# A4_INSAGE_01.net
KiCad netlist of a schematic drawn in Altium Designer
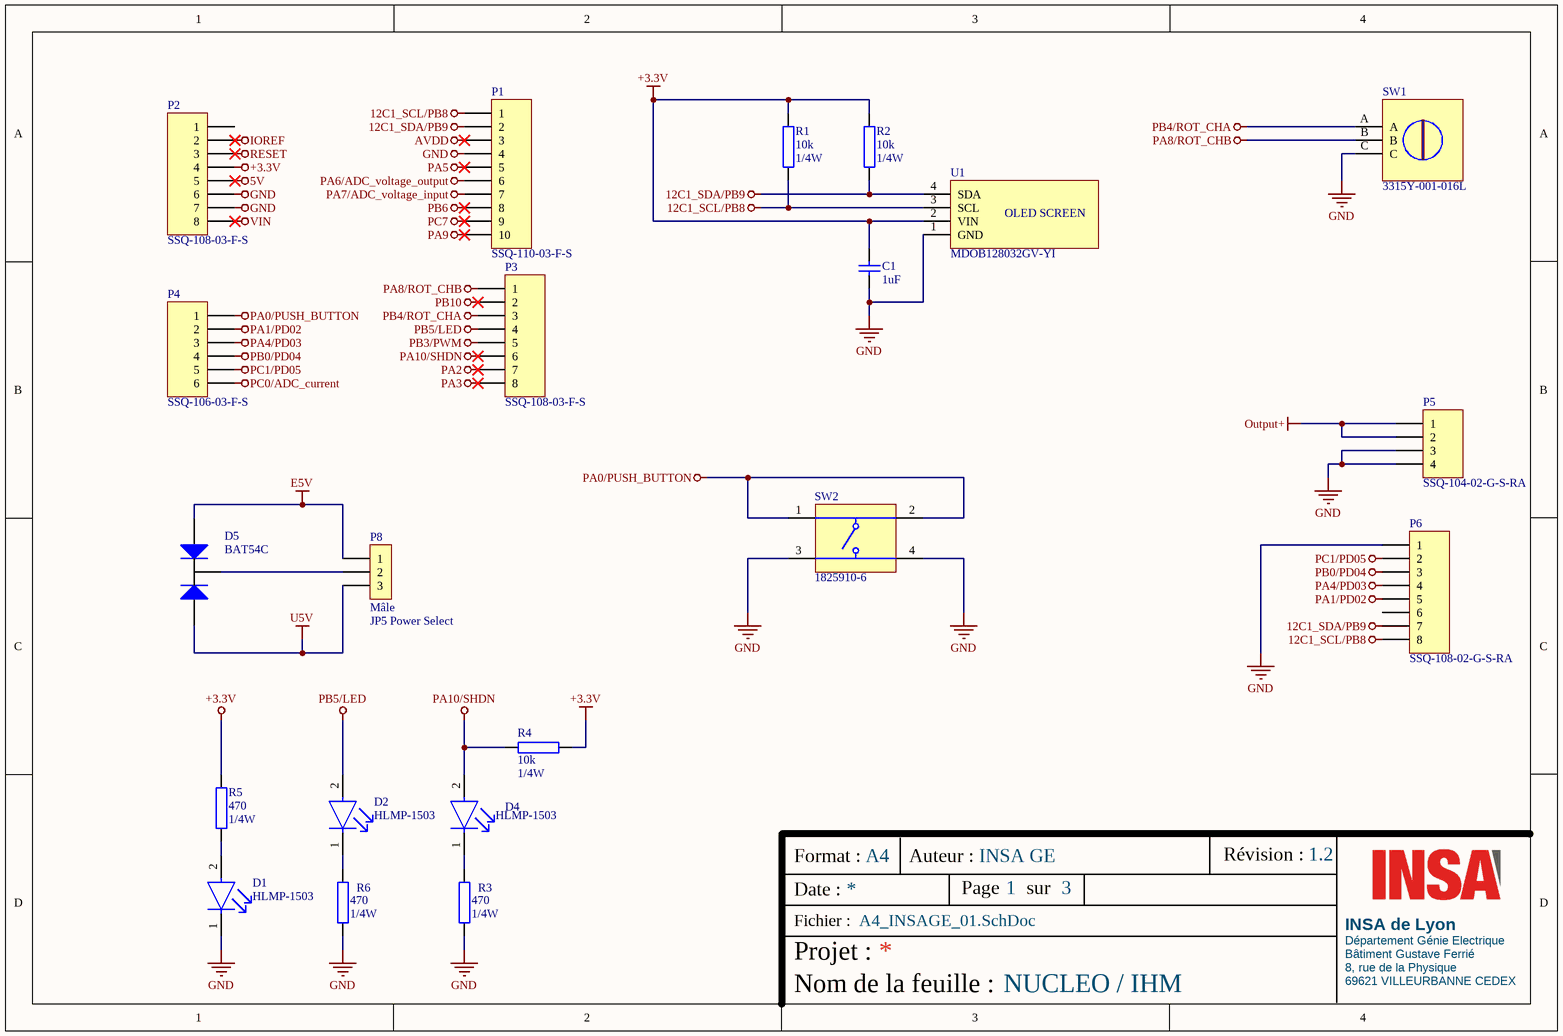
[diagram p0: A4_INSAGE_01.SchDoc]

(export (version "E")
  (design (tool "Eeschema 10.0.6"))
  (components
    (comp (ref "C1")
      (value "1uF")
      (footprint "1206_C")
      (fields (field (name "Comment") "Condensateur NON pol") (field (name "PUBLISHER") "Altium Limited"))
      (libsource (lib "Altium_CREATE_2026") (part "Condensateur NON pol"))
    )
    (comp (ref "D1")
      (value "HLMP-1503")
      (footprint "FP-HLMP-1503-MFG")
      (description "LED GREEN DIFFUSED T-1 T/H")
      (fields
        (field (name "MANUFACTURER") "Broadcom")
        (field (name "OCTOPART") "https://octopart.com/hlmp-1503-broadcom-71130371")
      )
      (libsource (lib "Altium_CREATE_2026") (part "CMP-18399-000010-1"))
    )
    (comp (ref "D2")
      (value "HLMP-1503")
      (footprint "FP-HLMP-1503-MFG")
      (description "LED GREEN DIFFUSED T-1 T/H")
      (fields
        (field (name "MANUFACTURER") "Broadcom")
        (field (name "OCTOPART") "https://octopart.com/hlmp-1503-broadcom-71130371")
      )
      (libsource (lib "Altium_CREATE_2026") (part "CMP-18399-000010-1"))
    )
    (comp (ref "D4")
      (value "HLMP-1503")
      (footprint "FP-HLMP-1503-MFG")
      (description "LED GREEN DIFFUSED T-1 T/H")
      (fields
        (field (name "MANUFACTURER") "Broadcom")
        (field (name "OCTOPART") "https://octopart.com/hlmp-1503-broadcom-71130371")
      )
      (libsource (lib "Altium_CREATE_2026") (part "CMP-18399-000010-1"))
    )
    (comp (ref "D5")
      (value "BAT54C")
      (footprint "SOT-23-3")
      (description "Double Small signal Schottky diodes")
      (libsource (lib "Altium_CREATE_2026") (part "BAT54C"))
    )
    (comp (ref "P1")
      (value "SSQ-110-03-F-S")
      (footprint "ARDUINO HDR1X10")
      (description "CONN RCPT 10POS 0.1 GOLD PCB")
      (fields (field (name "PUBLISHER") "Altium Limited"))
      (libsource (lib "Altium_CREATE_2026") (part "Header 10"))
    )
    (comp (ref "P2")
      (value "SSQ-108-03-F-S")
      (footprint "ARDUINO HDR1X8")
      (description "CONN RCPT 8POS 0.1 GOLD PCB")
      (fields (field (name "PUBLISHER") "Altium Limited"))
      (libsource (lib "") (part "Header 8_1"))
    )
    (comp (ref "P3")
      (value "SSQ-108-03-F-S")
      (footprint "ARDUINO HDR1X8")
      (description "CONN RCPT 8POS 0.1 GOLD PCB")
      (fields (field (name "PUBLISHER") "Altium Limited"))
      (libsource (lib "Altium_CREATE_2026") (part "Header 8"))
    )
    (comp (ref "P4")
      (value "SSQ-106-03-F-S")
      (footprint "ARDUINO HDR1X6")
      (description "CONN RCPT 6POS 0.1 GOLD PCB")
      (fields (field (name "PUBLISHER") "Altium Limited"))
      (libsource (lib "Altium_CREATE_2026") (part "Header 6"))
    )
    (comp (ref "P5")
      (value "SSQ-104-02-G-S-RA")
      (footprint "ARDUINO HDR1X4 - Coudé")
      (description "Header 4 Coudé")
      (fields (field (name "PUBLISHER") "Altium Limited"))
      (libsource (lib "Altium_CREATE_2026") (part "Header 4 Coudé"))
    )
    (comp (ref "P6")
      (value "SSQ-108-02-G-S-RA")
      (footprint "ARDUINO HDR1X8 - Coudé")
      (description "Header 8 Coudé")
      (fields (field (name "PUBLISHER") "Altium Limited"))
      (libsource (lib "Altium_CREATE_2026") (part "Header 8 Coudé"))
    )
    (comp (ref "P8")
      (value "JP5 Power Select")
      (footprint "3PINF100")
      (description "Barrette femelle 100mil 3 PIN 1 rangée")
      (fields (field (name "PUBLISHER") "Altium Limited"))
      (libsource (lib "Altium_CREATE_2026") (part "BarF100Mil3Con1R"))
    )
    (comp (ref "R1")
      (value "10k")
      (footprint "1206_R")
      (description "Resistor")
      (fields
        (field (name "PUISSANCE") "1/4W")
        (field (name "Comment") "Resistance")
        (field (name "PUBLISHER") "Altium Limited")
      )
      (libsource (lib "Altium_CREATE_2026") (part "Resistance"))
    )
    (comp (ref "R2")
      (value "10k")
      (footprint "1206_R")
      (description "Resistor")
      (fields
        (field (name "PUISSANCE") "1/4W")
        (field (name "Comment") "Resistance")
        (field (name "PUBLISHER") "Altium Limited")
      )
      (libsource (lib "Altium_CREATE_2026") (part "Resistance"))
    )
    (comp (ref "R3")
      (value "470")
      (footprint "1206_R")
      (description "Resistor")
      (fields
        (field (name "PUISSANCE") "1/4W")
        (field (name "Comment") "Resistance")
        (field (name "PUBLISHER") "Altium Limited")
      )
      (libsource (lib "Altium_CREATE_2026") (part "Resistance"))
    )
    (comp (ref "R4")
      (value "10k")
      (footprint "1206_R")
      (description "Resistor")
      (fields
        (field (name "PUISSANCE") "1/4W")
        (field (name "Comment") "Resistance")
        (field (name "PUBLISHER") "Altium Limited")
      )
      (libsource (lib "Altium_CREATE_2026") (part "Resistance"))
    )
    (comp (ref "R5")
      (value "470")
      (footprint "1206_R")
      (description "Resistor")
      (fields
        (field (name "PUISSANCE") "1/4W")
        (field (name "Comment") "Resistance")
        (field (name "PUBLISHER") "Altium Limited")
      )
      (libsource (lib "Altium_CREATE_2026") (part "Resistance"))
    )
    (comp (ref "R6")
      (value "470")
      (footprint "1206_R")
      (description "Resistor")
      (fields
        (field (name "PUISSANCE") "1/4W")
        (field (name "Comment") "Resistance")
        (field (name "PUBLISHER") "Altium Limited")
      )
      (libsource (lib "Altium_CREATE_2026") (part "Resistance"))
    )
    (comp (ref "SW1")
      (value "3315Y-001-016L")
      (footprint "ROTARY")
      (description "ROTARY ENCODER MECHANICAL 16PPR")
      (libsource (lib "Altium_CREATE_2026") (part "ROT ENCODER 3315Y-025-016L"))
    )
    (comp (ref "SW2")
      (value "1825910-6")
      (footprint "TECO-1825910-6_V")
      (description "SWITCH TACTILE SPST-NO 0.05A 24V")
      (fields (field (name "MANUFACTURER") "TE Connectivity"))
      (libsource (lib "Altium_CREATE_2026") (part "CMP-1684-00021-1"))
    )
    (comp (ref "U1")
      (value "MDOB128032GV-YI")
      (footprint "MDOB128032GV-YI")
      (description "GRAPHIC OLED 128x32 YELLOW 3V I2C")
      (libsource (lib "Altium_CREATE_2026") (part "SCREEN MDOB128032GV-YI"))
    )
  )
  (nets
    (net (code "1") (name "+3.3V") (class "Default")
      (node (ref "C1") (pin "2") (pinfunction "2_2") (pintype "passive"))
      (node (ref "P2") (pin "4") (pinfunction "4_4") (pintype "passive"))
      (node (ref "R1") (pin "2") (pinfunction "2_2") (pintype "passive"))
      (node (ref "R2") (pin "2") (pinfunction "2_2") (pintype "passive"))
      (node (ref "R4") (pin "2") (pinfunction "2_2") (pintype "passive"))
      (node (ref "R5") (pin "2") (pinfunction "2_2") (pintype "passive"))
      (node (ref "U1") (pin "2") (pinfunction "VIN_2") (pintype "passive"))
    )
    (net (code "2") (name "5V") (class "Default")
      (node (ref "P2") (pin "5") (pinfunction "5_5") (pintype "passive"))
    )
    (net (code "3") (name "12C1_SCL{slash}PB8") (class "Default")
      (node (ref "P1") (pin "1") (pinfunction "1_1") (pintype "passive"))
      (node (ref "P6") (pin "8") (pinfunction "8_8") (pintype "passive"))
      (node (ref "R1") (pin "1") (pinfunction "1_1") (pintype "passive"))
      (node (ref "U1") (pin "3") (pinfunction "SCL_3") (pintype "passive"))
    )
    (net (code "4") (name "12C1_SDA{slash}PB9") (class "Default")
      (node (ref "P1") (pin "2") (pinfunction "2_2") (pintype "passive"))
      (node (ref "P6") (pin "7") (pinfunction "7_7") (pintype "passive"))
      (node (ref "R2") (pin "1") (pinfunction "1_1") (pintype "passive"))
      (node (ref "U1") (pin "4") (pinfunction "SDA_4") (pintype "passive"))
    )
    (net (code "5") (name "AVDD") (class "Default")
      (node (ref "P1") (pin "3") (pinfunction "3_3") (pintype "passive"))
    )
    (net (code "6") (name "E5V") (class "Default")
      (node (ref "D5") (pin "1") (pinfunction "A1_1") (pintype "passive"))
      (node (ref "P8") (pin "1") (pinfunction "1_1") (pintype "passive"))
    )
    (net (code "7") (name "GND") (class "Default")
      (node (ref "C1") (pin "1") (pinfunction "1_1") (pintype "passive"))
      (node (ref "D1") (pin "1") (pinfunction "C_1") (pintype "passive"))
      (node (ref "P1") (pin "4") (pinfunction "4_4") (pintype "passive"))
      (node (ref "P2") (pin "6") (pinfunction "6_6") (pintype "passive"))
      (node (ref "P2") (pin "7") (pinfunction "7_7") (pintype "passive"))
      (node (ref "P5") (pin "3") (pinfunction "3_3") (pintype "passive"))
      (node (ref "P5") (pin "4") (pinfunction "4_4") (pintype "passive"))
      (node (ref "P6") (pin "1") (pinfunction "1_1") (pintype "passive"))
      (node (ref "R3") (pin "1") (pinfunction "1_1") (pintype "passive"))
      (node (ref "R6") (pin "1") (pinfunction "1_1") (pintype "passive"))
      (node (ref "SW1") (pin "C") (pinfunction "C_C") (pintype "passive"))
      (node (ref "SW2") (pin "3") (pinfunction "3_3") (pintype "passive"))
      (node (ref "SW2") (pin "4") (pinfunction "4_4") (pintype "passive"))
      (node (ref "U1") (pin "1") (pinfunction "GND_1") (pintype "passive"))
    )
    (net (code "8") (name "IOREF") (class "Default")
      (node (ref "P2") (pin "2") (pinfunction "2_2") (pintype "passive"))
    )
    (net (code "9") (name "Net-(D1-A)") (class "Default")
      (node (ref "D1") (pin "2") (pinfunction "A_2") (pintype "passive"))
      (node (ref "R5") (pin "1") (pinfunction "1_1") (pintype "passive"))
    )
    (net (code "10") (name "Net-(D2-C)") (class "Default")
      (node (ref "D2") (pin "1") (pinfunction "C_1") (pintype "passive"))
      (node (ref "R6") (pin "2") (pinfunction "2_2") (pintype "passive"))
    )
    (net (code "11") (name "Net-(D4-C)") (class "Default")
      (node (ref "D4") (pin "1") (pinfunction "C_1") (pintype "passive"))
      (node (ref "R3") (pin "2") (pinfunction "2_2") (pintype "passive"))
    )
    (net (code "12") (name "Net-(D5-K)") (class "Default")
      (node (ref "D5") (pin "3") (pinfunction "K_3") (pintype "passive"))
      (node (ref "P8") (pin "2") (pinfunction "2_2") (pintype "passive"))
    )
    (net (code "13") (name "Output+") (class "Default")
      (node (ref "P5") (pin "1") (pinfunction "1_1") (pintype "passive"))
      (node (ref "P5") (pin "2") (pinfunction "2_2") (pintype "passive"))
    )
    (net (code "14") (name "PA0{slash}PUSH_BUTTON") (class "Default")
      (node (ref "P4") (pin "1") (pinfunction "1_1") (pintype "passive"))
      (node (ref "SW2") (pin "1") (pinfunction "1_1") (pintype "passive"))
      (node (ref "SW2") (pin "2") (pinfunction "2_2") (pintype "passive"))
    )
    (net (code "15") (name "PA1{slash}PD02") (class "Default")
      (node (ref "P4") (pin "2") (pinfunction "2_2") (pintype "passive"))
      (node (ref "P6") (pin "5") (pinfunction "5_5") (pintype "passive"))
    )
    (net (code "16") (name "PA2") (class "Default")
      (node (ref "P3") (pin "7") (pinfunction "7_7") (pintype "passive"))
    )
    (net (code "17") (name "PA3") (class "Default")
      (node (ref "P3") (pin "8") (pinfunction "8_8") (pintype "passive"))
    )
    (net (code "18") (name "PA4{slash}PD03") (class "Default")
      (node (ref "P4") (pin "3") (pinfunction "3_3") (pintype "passive"))
      (node (ref "P6") (pin "4") (pinfunction "4_4") (pintype "passive"))
    )
    (net (code "19") (name "PA5") (class "Default")
      (node (ref "P1") (pin "5") (pinfunction "5_5") (pintype "passive"))
    )
    (net (code "20") (name "PA6{slash}ADC_voltage_output") (class "Default")
      (node (ref "P1") (pin "6") (pinfunction "6_6") (pintype "passive"))
    )
    (net (code "21") (name "PA7{slash}ADC_voltage_input") (class "Default")
      (node (ref "P1") (pin "7") (pinfunction "7_7") (pintype "passive"))
    )
    (net (code "22") (name "PA8{slash}ROT_CHB") (class "Default")
      (node (ref "P3") (pin "1") (pinfunction "1_1") (pintype "passive"))
      (node (ref "SW1") (pin "B") (pinfunction "B_B") (pintype "passive"))
    )
    (net (code "23") (name "PA9") (class "Default")
      (node (ref "P1") (pin "10") (pinfunction "10_10") (pintype "passive"))
    )
    (net (code "24") (name "PA10{slash}SHDN") (class "Default")
      (node (ref "D4") (pin "2") (pinfunction "A_2") (pintype "passive"))
      (node (ref "P3") (pin "6") (pinfunction "6_6") (pintype "passive"))
      (node (ref "R4") (pin "1") (pinfunction "1_1") (pintype "passive"))
    )
    (net (code "25") (name "PB0{slash}PD04") (class "Default")
      (node (ref "P4") (pin "4") (pinfunction "4_4") (pintype "passive"))
      (node (ref "P6") (pin "3") (pinfunction "3_3") (pintype "passive"))
    )
    (net (code "26") (name "PB3{slash}PWM") (class "Default")
      (node (ref "P3") (pin "5") (pinfunction "5_5") (pintype "passive"))
    )
    (net (code "27") (name "PB4{slash}ROT_CHA") (class "Default")
      (node (ref "P3") (pin "3") (pinfunction "3_3") (pintype "passive"))
      (node (ref "SW1") (pin "A") (pinfunction "A_A") (pintype "passive"))
    )
    (net (code "28") (name "PB5{slash}LED") (class "Default")
      (node (ref "D2") (pin "2") (pinfunction "A_2") (pintype "passive"))
      (node (ref "P3") (pin "4") (pinfunction "4_4") (pintype "passive"))
    )
    (net (code "29") (name "PB6") (class "Default")
      (node (ref "P1") (pin "8") (pinfunction "8_8") (pintype "passive"))
    )
    (net (code "30") (name "PB10") (class "Default")
      (node (ref "P3") (pin "2") (pinfunction "2_2") (pintype "passive"))
    )
    (net (code "31") (name "PC0{slash}ADC_current") (class "Default")
      (node (ref "P4") (pin "6") (pinfunction "6_6") (pintype "passive"))
    )
    (net (code "32") (name "PC1{slash}PD05") (class "Default")
      (node (ref "P4") (pin "5") (pinfunction "5_5") (pintype "passive"))
      (node (ref "P6") (pin "2") (pinfunction "2_2") (pintype "passive"))
    )
    (net (code "33") (name "PC7") (class "Default")
      (node (ref "P1") (pin "9") (pinfunction "9_9") (pintype "passive"))
    )
    (net (code "34") (name "RESET") (class "Default")
      (node (ref "P2") (pin "3") (pinfunction "3_3") (pintype "passive"))
    )
    (net (code "35") (name "U5V") (class "Default")
      (node (ref "D5") (pin "2") (pinfunction "A2_2") (pintype "passive"))
      (node (ref "P8") (pin "3") (pinfunction "3_3") (pintype "passive"))
    )
    (net (code "36") (name "VIN") (class "Default")
      (node (ref "P2") (pin "8") (pinfunction "8_8") (pintype "passive"))
    )
    (net (code "37") (name "unconnected-(P2-Pad1)") (class "Default")
      (node (ref "P2") (pin "1") (pinfunction "1_1") (pintype "passive"))
    )
    (net (code "38") (name "unconnected-(P6-Pad6)") (class "Default")
      (node (ref "P6") (pin "6") (pinfunction "6_6") (pintype "passive"))
    )
  )
)
